# rfid.net
KiCad netlist of a schematic drawn in Altium Designer
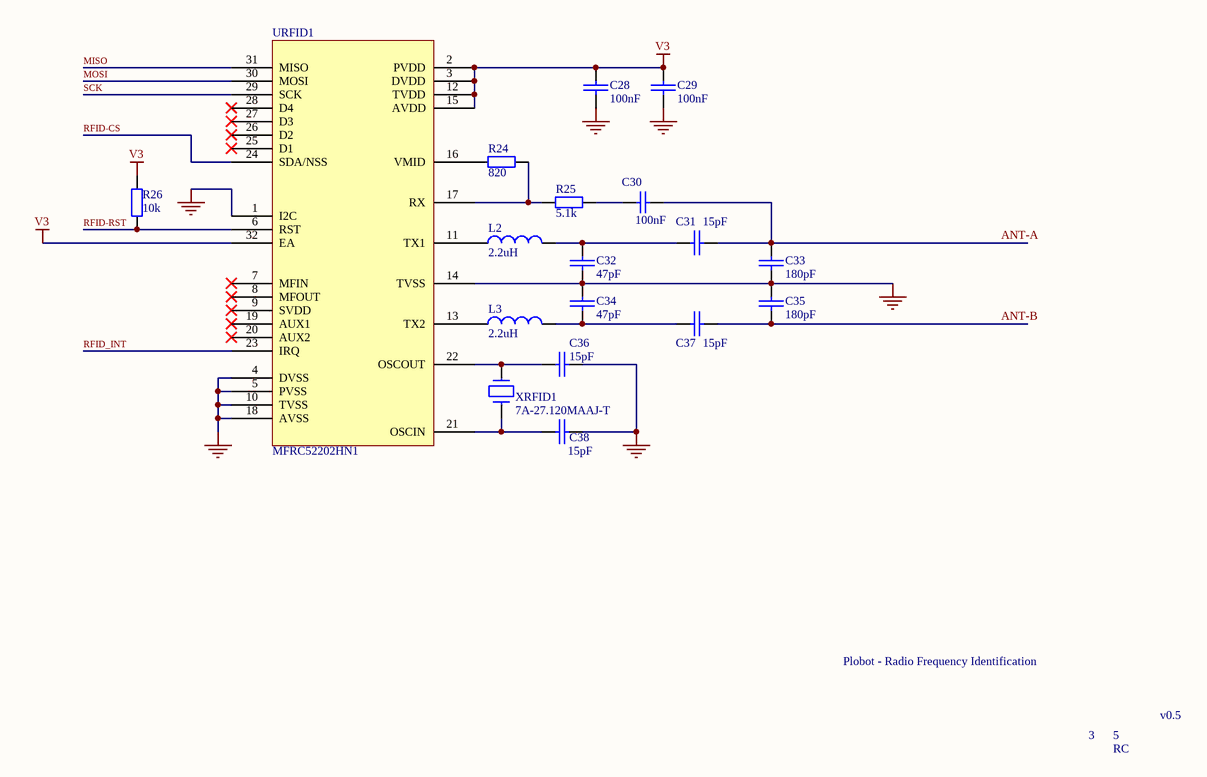
[diagram p0: rfid.SchDoc]

(export (version "E")
  (design (tool "Eeschema 10.0.6"))
  (components
    (comp (ref "C28")
      (value "100nF")
      (footprint "plobot_review:CAPC1608N")
      (description "Capacitor")
      (libsource (lib "") (part "Cap_1"))
    )
    (comp (ref "C29")
      (value "100nF")
      (footprint "plobot_review:CAPC1608N")
      (description "Capacitor")
      (libsource (lib "") (part "Cap_1"))
    )
    (comp (ref "C30")
      (value "100nF")
      (footprint "plobot_review:CAPC1608N")
      (description "Capacitor")
      (fields (field (name "PUBLISHER") "Altium Limited"))
      (libsource (lib "*") (part "Cap"))
    )
    (comp (ref "C31")
      (value "15pF")
      (footprint "plobot_review:CAPC1608N")
      (description "Capacitor")
      (libsource (lib "") (part "Cap_1"))
    )
    (comp (ref "C32")
      (value "47pF")
      (footprint "plobot_review:CAPC1608N")
      (description "Capacitor")
      (libsource (lib "") (part "Cap_1"))
    )
    (comp (ref "C33")
      (value "180pF")
      (footprint "plobot_review:CAPC1608N")
      (description "Capacitor")
      (libsource (lib "") (part "Cap_1"))
    )
    (comp (ref "C34")
      (value "47pF")
      (footprint "plobot_review:CAPC1608N")
      (description "Capacitor")
      (libsource (lib "") (part "Cap_1"))
    )
    (comp (ref "C35")
      (value "180pF")
      (footprint "plobot_review:CAPC1608N")
      (description "Capacitor")
      (libsource (lib "") (part "Cap_1"))
    )
    (comp (ref "C36")
      (value "15pF")
      (footprint "plobot_review:CAPC1608N")
      (description "Capacitor")
      (libsource (lib "*") (part "CAP"))
    )
    (comp (ref "C37")
      (value "15pF")
      (footprint "plobot_review:CAPC1608N")
      (description "Capacitor")
      (libsource (lib "") (part "Cap_1"))
    )
    (comp (ref "C38")
      (value "15pF")
      (footprint "plobot_review:CAPC1608N")
      (description "Capacitor")
      (libsource (lib "*") (part "CAP"))
    )
    (comp (ref "L2")
      (value "2.2uH")
      (footprint "plobot_review:INDC1608N")
      (description "Inductor")
      (fields (field (name "PUBLISHER") "Altium Limited"))
      (libsource (lib "Miscellaneous Devices") (part "Inductor"))
    )
    (comp (ref "L3")
      (value "2.2uH")
      (footprint "plobot_review:INDC1608N")
      (description "Inductor")
      (fields (field (name "PUBLISHER") "Altium Limited"))
      (libsource (lib "Miscellaneous Devices") (part "Inductor"))
    )
    (comp (ref "R24")
      (value "820")
      (footprint "plobot_review:RESC1608N")
      (description "Resistor")
      (fields (field (name "PUBLISHER") "Altium Limited"))
      (libsource (lib "*") (part "Res2"))
    )
    (comp (ref "R25")
      (value "5.1k")
      (footprint "plobot_review:RESC1608N")
      (description "Resistor")
      (fields (field (name "PUBLISHER") "Altium Limited"))
      (libsource (lib "*") (part "Res2"))
    )
    (comp (ref "R26")
      (value "10k")
      (footprint "plobot_review:RESC1608N")
      (description "Resistor")
      (fields (field (name "PUBLISHER") "Altium Limited"))
      (libsource (lib "") (part "Res2_1"))
    )
    (comp (ref "URFID1")
      (value "MFRC52202HN1")
      (footprint "plobot_review:MFRC52202HN1")
      (libsource (lib "components") (part "MFRC52202HN1"))
    )
    (comp (ref "XRFID1")
      (value "7A-27.120MAAJ-T")
      (footprint "plobot_review:XTAL")
      (libsource (lib "*") (part "Tm08B.S01_12M_42"))
    )
  )
  (nets
    (net (code "1") (name "/ANT-A") (class "Default")
      (node (ref "C30") (pin "2") (pinfunction "2_2") (pintype "passive"))
      (node (ref "C31") (pin "2") (pinfunction "2_2") (pintype "passive"))
      (node (ref "C33") (pin "2") (pinfunction "2_2") (pintype "passive"))
    )
    (net (code "2") (name "/ANT-B") (class "Default")
      (node (ref "C35") (pin "1") (pinfunction "1_1") (pintype "passive"))
      (node (ref "C37") (pin "2") (pinfunction "2_2") (pintype "passive"))
    )
    (net (code "3") (name "/MISO") (class "Default")
      (node (ref "URFID1") (pin "31") (pinfunction "MISO_31") (pintype "passive"))
    )
    (net (code "4") (name "/MOSI") (class "Default")
      (node (ref "URFID1") (pin "30") (pinfunction "MOSI_30") (pintype "passive"))
    )
    (net (code "5") (name "/RFID-CS") (class "Default")
      (node (ref "URFID1") (pin "24") (pinfunction "SDA/NSS_24") (pintype "passive"))
    )
    (net (code "6") (name "/RFID-RST") (class "Default")
      (node (ref "R26") (pin "2") (pinfunction "2_2") (pintype "passive"))
      (node (ref "URFID1") (pin "6") (pinfunction "RST_6") (pintype "passive"))
    )
    (net (code "7") (name "/RFID_INT") (class "Default")
      (node (ref "URFID1") (pin "23") (pinfunction "IRQ_23") (pintype "passive"))
    )
    (net (code "8") (name "/SCK") (class "Default")
      (node (ref "URFID1") (pin "29") (pinfunction "SCK_29") (pintype "passive"))
    )
    (net (code "9") (name "GND") (class "Default")
      (node (ref "C28") (pin "1") (pinfunction "1_1") (pintype "passive"))
      (node (ref "C29") (pin "1") (pinfunction "1_1") (pintype "passive"))
      (node (ref "C32") (pin "1") (pinfunction "1_1") (pintype "passive"))
      (node (ref "C33") (pin "1") (pinfunction "1_1") (pintype "passive"))
      (node (ref "C34") (pin "2") (pinfunction "2_2") (pintype "passive"))
      (node (ref "C35") (pin "2") (pinfunction "2_2") (pintype "passive"))
      (node (ref "C36") (pin "2") (pinfunction "2_2") (pintype "passive"))
      (node (ref "C38") (pin "2") (pinfunction "2_2") (pintype "passive"))
      (node (ref "URFID1") (pin "1") (pinfunction "I2C_1") (pintype "passive"))
      (node (ref "URFID1") (pin "10") (pinfunction "TVSS_10") (pintype "passive"))
      (node (ref "URFID1") (pin "14") (pinfunction "TVSS_14") (pintype "passive"))
      (node (ref "URFID1") (pin "18") (pinfunction "AVSS_18") (pintype "passive"))
      (node (ref "URFID1") (pin "4") (pinfunction "DVSS_4") (pintype "passive"))
      (node (ref "URFID1") (pin "5") (pinfunction "PVSS_5") (pintype "passive"))
    )
    (net (code "10") (name "Net-(C30-Pad1)") (class "Default")
      (node (ref "C30") (pin "1") (pinfunction "1_1") (pintype "passive"))
      (node (ref "R25") (pin "1") (pinfunction "1_1") (pintype "passive"))
    )
    (net (code "11") (name "Net-(C31-Pad1)") (class "Default")
      (node (ref "C31") (pin "1") (pinfunction "1_1") (pintype "passive"))
      (node (ref "C32") (pin "2") (pinfunction "2_2") (pintype "passive"))
      (node (ref "L2") (pin "2") (pinfunction "2_2") (pintype "passive"))
    )
    (net (code "12") (name "Net-(C34-Pad1)") (class "Default")
      (node (ref "C34") (pin "1") (pinfunction "1_1") (pintype "passive"))
      (node (ref "C37") (pin "1") (pinfunction "1_1") (pintype "passive"))
      (node (ref "L3") (pin "2") (pinfunction "2_2") (pintype "passive"))
    )
    (net (code "13") (name "Net-(URFID1-OSCIN)") (class "Default")
      (node (ref "C38") (pin "1") (pinfunction "1_1") (pintype "passive"))
      (node (ref "URFID1") (pin "21") (pinfunction "OSCIN_21") (pintype "passive"))
      (node (ref "XRFID1") (pin "1") (pintype "passive"))
    )
    (net (code "14") (name "Net-(URFID1-OSCOUT)") (class "Default")
      (node (ref "C36") (pin "1") (pinfunction "1_1") (pintype "passive"))
      (node (ref "URFID1") (pin "22") (pinfunction "OSCOUT_22") (pintype "passive"))
      (node (ref "XRFID1") (pin "2") (pintype "passive"))
    )
    (net (code "15") (name "Net-(URFID1-RX)") (class "Default")
      (node (ref "R24") (pin "1") (pinfunction "1_1") (pintype "passive"))
      (node (ref "R25") (pin "2") (pinfunction "2_2") (pintype "passive"))
      (node (ref "URFID1") (pin "17") (pinfunction "RX_17") (pintype "passive"))
    )
    (net (code "16") (name "Net-(URFID1-TX1)") (class "Default")
      (node (ref "L2") (pin "1") (pinfunction "1_1") (pintype "passive"))
      (node (ref "URFID1") (pin "11") (pinfunction "TX1_11") (pintype "passive"))
    )
    (net (code "17") (name "Net-(URFID1-TX2)") (class "Default")
      (node (ref "L3") (pin "1") (pinfunction "1_1") (pintype "passive"))
      (node (ref "URFID1") (pin "13") (pinfunction "TX2_13") (pintype "passive"))
    )
    (net (code "18") (name "Net-(URFID1-VMID)") (class "Default")
      (node (ref "R24") (pin "2") (pinfunction "2_2") (pintype "passive"))
      (node (ref "URFID1") (pin "16") (pinfunction "VMID_16") (pintype "passive"))
    )
    (net (code "19") (name "V3") (class "Default")
      (node (ref "C28") (pin "2") (pinfunction "2_2") (pintype "passive"))
      (node (ref "C29") (pin "2") (pinfunction "2_2") (pintype "passive"))
      (node (ref "R26") (pin "1") (pinfunction "1_1") (pintype "passive"))
      (node (ref "URFID1") (pin "12") (pinfunction "TVDD_12") (pintype "passive"))
      (node (ref "URFID1") (pin "15") (pinfunction "AVDD_15") (pintype "passive"))
      (node (ref "URFID1") (pin "2") (pinfunction "PVDD_2") (pintype "passive"))
      (node (ref "URFID1") (pin "3") (pinfunction "DVDD_3") (pintype "passive"))
      (node (ref "URFID1") (pin "32") (pinfunction "EA_32") (pintype "passive"))
    )
    (net (code "20") (name "unconnected-(URFID1-AUX1-Pad19)") (class "Default")
      (node (ref "URFID1") (pin "19") (pinfunction "AUX1_19") (pintype "passive+no_connect"))
    )
    (net (code "21") (name "unconnected-(URFID1-AUX2-Pad20)") (class "Default")
      (node (ref "URFID1") (pin "20") (pinfunction "AUX2_20") (pintype "passive+no_connect"))
    )
    (net (code "22") (name "unconnected-(URFID1-D1-Pad25)") (class "Default")
      (node (ref "URFID1") (pin "25") (pinfunction "D1_25") (pintype "passive+no_connect"))
    )
    (net (code "23") (name "unconnected-(URFID1-D2-Pad26)") (class "Default")
      (node (ref "URFID1") (pin "26") (pinfunction "D2_26") (pintype "passive+no_connect"))
    )
    (net (code "24") (name "unconnected-(URFID1-D3-Pad27)") (class "Default")
      (node (ref "URFID1") (pin "27") (pinfunction "D3_27") (pintype "passive+no_connect"))
    )
    (net (code "25") (name "unconnected-(URFID1-D4-Pad28)") (class "Default")
      (node (ref "URFID1") (pin "28") (pinfunction "D4_28") (pintype "passive+no_connect"))
    )
    (net (code "26") (name "unconnected-(URFID1-MFIN-Pad7)") (class "Default")
      (node (ref "URFID1") (pin "7") (pinfunction "MFIN_7") (pintype "passive+no_connect"))
    )
    (net (code "27") (name "unconnected-(URFID1-MFOUT-Pad8)") (class "Default")
      (node (ref "URFID1") (pin "8") (pinfunction "MFOUT_8") (pintype "passive+no_connect"))
    )
    (net (code "28") (name "unconnected-(URFID1-SVDD-Pad9)") (class "Default")
      (node (ref "URFID1") (pin "9") (pinfunction "SVDD_9") (pintype "passive+no_connect"))
    )
  )
)
